# reLoaD_Base.net
KiCad netlist of a schematic drawn in EAGLE
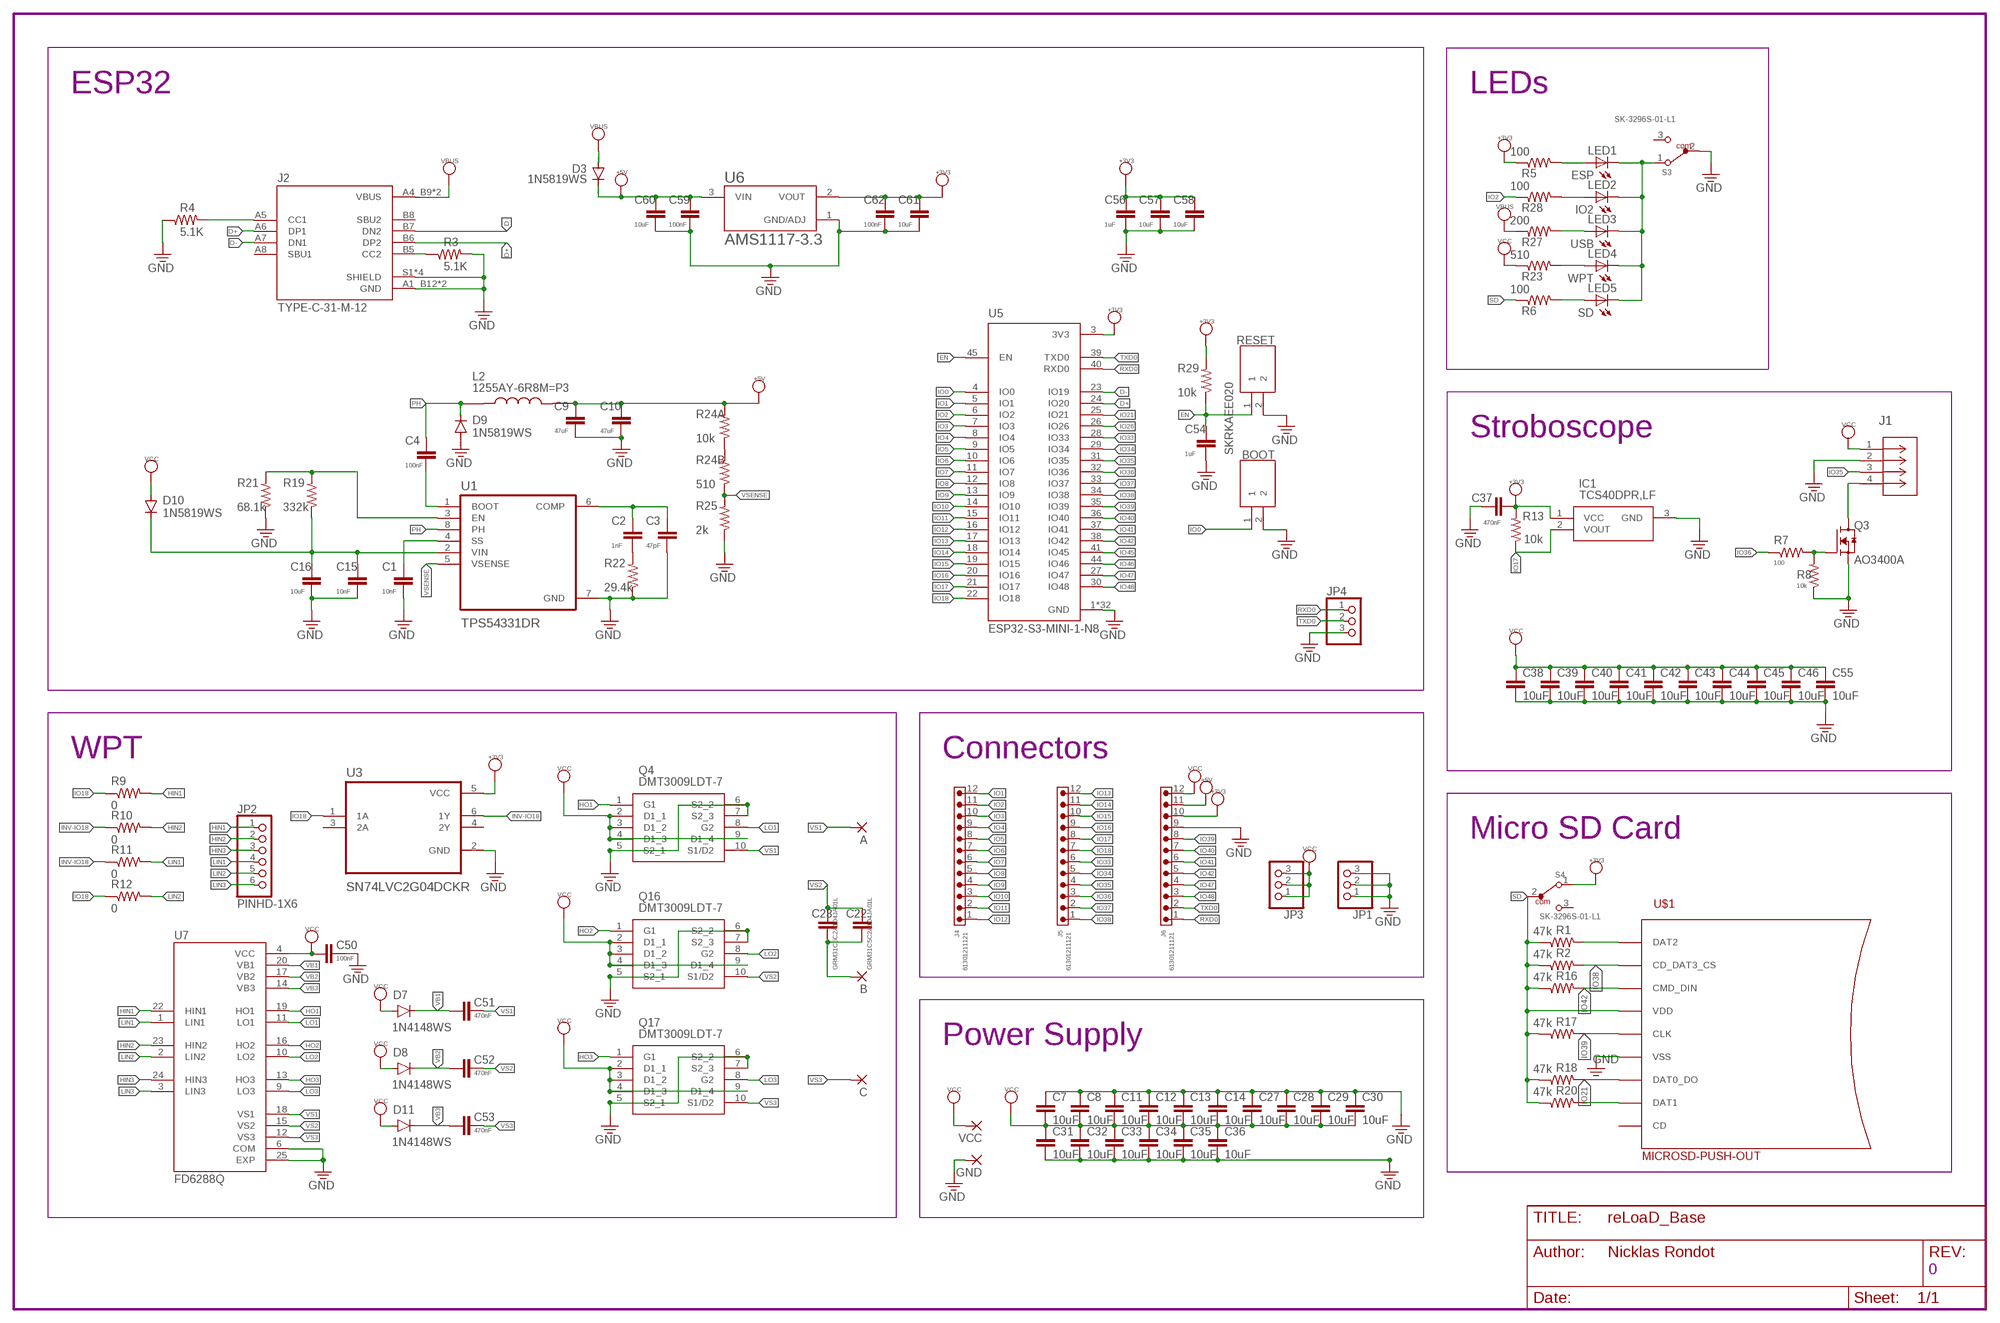
[diagram p0: schematic, sheet 1]

(export (version "E")
  (design (tool "Eeschema 10.0.6"))
  (components
    (comp (ref "A")
      (value "3,81/1,4")
      (footprint "eagle-import:3,81_1,4")
      (libsource (lib "eagle-import") (part "3,81/1,4"))
    )
    (comp (ref "B")
      (value "3,81/1,4")
      (footprint "eagle-import:3,81_1,4")
      (libsource (lib "eagle-import") (part "3,81/1,4"))
    )
    (comp (ref "BOOT")
      (value "SKRKAEE020")
      (footprint "eagle-import:SKRKAEE020")
      (fields (field (name "MOUSER_PART_NUMBER") "688-SKRKAEE020"))
      (libsource (lib "eagle-import") (part "SKRKAEE020"))
    )
    (comp (ref "C")
      (value "3,81/1,4")
      (footprint "eagle-import:3,81_1,4")
      (libsource (lib "eagle-import") (part "3,81/1,4"))
    )
    (comp (ref "C1")
      (value "10nF")
      (footprint "eagle-import:C0603K")
      (libsource (lib "eagle-import") (part "resistor_348_C-EUC0603K"))
    )
    (comp (ref "C2")
      (value "1nF")
      (footprint "eagle-import:C0603K")
      (libsource (lib "eagle-import") (part "resistor_348_C-EUC0603K"))
    )
    (comp (ref "C3")
      (value "47pF")
      (footprint "eagle-import:C0603K")
      (libsource (lib "eagle-import") (part "resistor_348_C-EUC0603K"))
    )
    (comp (ref "C4")
      (value "100nF")
      (footprint "eagle-import:C0603K")
      (libsource (lib "eagle-import") (part "resistor_348_C-EUC0603K"))
    )
    (comp (ref "C7")
      (value "10uF")
      (footprint "eagle-import:C0805K")
      (libsource (lib "eagle-import") (part "C-EUC0805K"))
    )
    (comp (ref "C8")
      (value "10uF")
      (footprint "eagle-import:C0805K")
      (libsource (lib "eagle-import") (part "C-EUC0805K"))
    )
    (comp (ref "C9")
      (value "47uF")
      (footprint "eagle-import:C0603K")
      (libsource (lib "eagle-import") (part "resistor_348_C-EUC0603K"))
    )
    (comp (ref "C10")
      (value "47uF")
      (footprint "eagle-import:C0603K")
      (libsource (lib "eagle-import") (part "resistor_348_C-EUC0603K"))
    )
    (comp (ref "C11")
      (value "10uF")
      (footprint "eagle-import:C0805K")
      (libsource (lib "eagle-import") (part "C-EUC0805K"))
    )
    (comp (ref "C12")
      (value "10uF")
      (footprint "eagle-import:C0805K")
      (libsource (lib "eagle-import") (part "C-EUC0805K"))
    )
    (comp (ref "C13")
      (value "10uF")
      (footprint "eagle-import:C0805K")
      (libsource (lib "eagle-import") (part "C-EUC0805K"))
    )
    (comp (ref "C14")
      (value "10uF")
      (footprint "eagle-import:C0805K")
      (libsource (lib "eagle-import") (part "C-EUC0805K"))
    )
    (comp (ref "C15")
      (value "10nF")
      (footprint "eagle-import:C0603K")
      (libsource (lib "eagle-import") (part "resistor_348_C-EUC0603K"))
    )
    (comp (ref "C16")
      (value "10uF")
      (footprint "eagle-import:C0603K")
      (libsource (lib "eagle-import") (part "resistor_348_C-EUC0603K"))
    )
    (comp (ref "C22")
      (value "GRM31C5C2A104JA01L")
      (footprint "eagle-import:C1206K")
      (libsource (lib "eagle-import") (part "C-EUC1206K"))
    )
    (comp (ref "C23")
      (value "GRM31C5C2A104JA01L")
      (footprint "eagle-import:C1206K")
      (libsource (lib "eagle-import") (part "C-EUC1206K"))
    )
    (comp (ref "C27")
      (value "10uF")
      (footprint "eagle-import:C0805K")
      (libsource (lib "eagle-import") (part "C-EUC0805K"))
    )
    (comp (ref "C28")
      (value "10uF")
      (footprint "eagle-import:C0805K")
      (libsource (lib "eagle-import") (part "C-EUC0805K"))
    )
    (comp (ref "C29")
      (value "10uF")
      (footprint "eagle-import:C0805K")
      (libsource (lib "eagle-import") (part "C-EUC0805K"))
    )
    (comp (ref "C30")
      (value "10uF")
      (footprint "eagle-import:C0805K")
      (libsource (lib "eagle-import") (part "C-EUC0805K"))
    )
    (comp (ref "C31")
      (value "10uF")
      (footprint "eagle-import:C0805K")
      (libsource (lib "eagle-import") (part "C-EUC0805K"))
    )
    (comp (ref "C32")
      (value "10uF")
      (footprint "eagle-import:C0805K")
      (libsource (lib "eagle-import") (part "C-EUC0805K"))
    )
    (comp (ref "C33")
      (value "10uF")
      (footprint "eagle-import:C0805K")
      (libsource (lib "eagle-import") (part "C-EUC0805K"))
    )
    (comp (ref "C34")
      (value "10uF")
      (footprint "eagle-import:C0805K")
      (libsource (lib "eagle-import") (part "C-EUC0805K"))
    )
    (comp (ref "C35")
      (value "10uF")
      (footprint "eagle-import:C0805K")
      (libsource (lib "eagle-import") (part "C-EUC0805K"))
    )
    (comp (ref "C36")
      (value "10uF")
      (footprint "eagle-import:C0805K")
      (libsource (lib "eagle-import") (part "C-EUC0805K"))
    )
    (comp (ref "C37")
      (value "470nF")
      (footprint "eagle-import:C0603K")
      (libsource (lib "eagle-import") (part "resistor_348_C-EUC0603K"))
    )
    (comp (ref "C38")
      (value "10uF")
      (footprint "eagle-import:C0805K")
      (libsource (lib "eagle-import") (part "C-EUC0805K"))
    )
    (comp (ref "C39")
      (value "10uF")
      (footprint "eagle-import:C0805K")
      (libsource (lib "eagle-import") (part "C-EUC0805K"))
    )
    (comp (ref "C40")
      (value "10uF")
      (footprint "eagle-import:C0805K")
      (libsource (lib "eagle-import") (part "C-EUC0805K"))
    )
    (comp (ref "C41")
      (value "10uF")
      (footprint "eagle-import:C0805K")
      (libsource (lib "eagle-import") (part "C-EUC0805K"))
    )
    (comp (ref "C42")
      (value "10uF")
      (footprint "eagle-import:C0805K")
      (libsource (lib "eagle-import") (part "C-EUC0805K"))
    )
    (comp (ref "C43")
      (value "10uF")
      (footprint "eagle-import:C0805K")
      (libsource (lib "eagle-import") (part "C-EUC0805K"))
    )
    (comp (ref "C44")
      (value "10uF")
      (footprint "eagle-import:C0805K")
      (libsource (lib "eagle-import") (part "C-EUC0805K"))
    )
    (comp (ref "C45")
      (value "10uF")
      (footprint "eagle-import:C0805K")
      (libsource (lib "eagle-import") (part "C-EUC0805K"))
    )
    (comp (ref "C46")
      (value "10uF")
      (footprint "eagle-import:C0805K")
      (libsource (lib "eagle-import") (part "C-EUC0805K"))
    )
    (comp (ref "C50")
      (value "100nF")
      (footprint "eagle-import:C0603K")
      (libsource (lib "eagle-import") (part "resistor_348_C-EUC0603K"))
    )
    (comp (ref "C51")
      (value "470nF")
      (footprint "eagle-import:C0603K")
      (libsource (lib "eagle-import") (part "resistor_348_C-EUC0603K"))
    )
    (comp (ref "C52")
      (value "470nF")
      (footprint "eagle-import:C0603K")
      (libsource (lib "eagle-import") (part "resistor_348_C-EUC0603K"))
    )
    (comp (ref "C53")
      (value "470nF")
      (footprint "eagle-import:C0603K")
      (libsource (lib "eagle-import") (part "resistor_348_C-EUC0603K"))
    )
    (comp (ref "C54")
      (value "1uF")
      (footprint "eagle-import:C0603K")
      (libsource (lib "eagle-import") (part "resistor_348_C-EUC0603K"))
    )
    (comp (ref "C55")
      (value "10uF")
      (footprint "eagle-import:C0805K")
      (libsource (lib "eagle-import") (part "C-EUC0805K"))
    )
    (comp (ref "C56")
      (value "1uF")
      (footprint "eagle-import:C0603K")
      (libsource (lib "eagle-import") (part "resistor_348_C-EUC0603K"))
    )
    (comp (ref "C57")
      (value "10uF")
      (footprint "eagle-import:C0603K")
      (libsource (lib "eagle-import") (part "resistor_348_C-EUC0603K"))
    )
    (comp (ref "C58")
      (value "10uF")
      (footprint "eagle-import:C0603K")
      (libsource (lib "eagle-import") (part "resistor_348_C-EUC0603K"))
    )
    (comp (ref "C59")
      (value "100nF")
      (footprint "eagle-import:C0603K")
      (libsource (lib "eagle-import") (part "resistor_348_C-EUC0603K"))
    )
    (comp (ref "C60")
      (value "10uF")
      (footprint "eagle-import:C0603K")
      (libsource (lib "eagle-import") (part "resistor_348_C-EUC0603K"))
    )
    (comp (ref "C61")
      (value "10uF")
      (footprint "eagle-import:C0603K")
      (libsource (lib "eagle-import") (part "resistor_348_C-EUC0603K"))
    )
    (comp (ref "C62")
      (value "100nF")
      (footprint "eagle-import:C0603K")
      (libsource (lib "eagle-import") (part "resistor_348_C-EUC0603K"))
    )
    (comp (ref "D3")
      (value "1N5819WS")
      (footprint "eagle-import:SOD323-W")
      (libsource (lib "eagle-import") (part "DIODE-SOD323-W"))
    )
    (comp (ref "D7")
      (value "1N4148WS")
      (footprint "eagle-import:SOD-323")
      (fields
        (field (name "DIGIKEY_PART_NUMBER") "1N4148WSFSTR-ND")
        (field (name "MANUFACTURER") "Diodes Incorporated")
        (field (name "CREATED_BY") "PCBLayout.com")
      )
      (libsource (lib "eagle-import") (part "1N4148WS"))
    )
    (comp (ref "D8")
      (value "1N4148WS")
      (footprint "eagle-import:SOD-323")
      (fields
        (field (name "DIGIKEY_PART_NUMBER") "1N4148WSFSTR-ND")
        (field (name "MANUFACTURER") "Diodes Incorporated")
        (field (name "CREATED_BY") "PCBLayout.com")
      )
      (libsource (lib "eagle-import") (part "1N4148WS"))
    )
    (comp (ref "D9")
      (value "1N5819WS")
      (footprint "eagle-import:SOD323-W")
      (libsource (lib "eagle-import") (part "DIODE-SOD323-W"))
    )
    (comp (ref "D10")
      (value "1N5819WS")
      (footprint "eagle-import:SOD323-W")
      (libsource (lib "eagle-import") (part "DIODE-SOD323-W"))
    )
    (comp (ref "D11")
      (value "1N4148WS")
      (footprint "eagle-import:SOD-323")
      (fields
        (field (name "DIGIKEY_PART_NUMBER") "1N4148WSFSTR-ND")
        (field (name "MANUFACTURER") "Diodes Incorporated")
        (field (name "CREATED_BY") "PCBLayout.com")
      )
      (libsource (lib "eagle-import") (part "1N4148WS"))
    )
    (comp (ref "GND")
      (value "3,81/1,4")
      (footprint "eagle-import:3,81_1,4")
      (libsource (lib "eagle-import") (part "3,81/1,4"))
    )
    (comp (ref "IC1")
      (value "TCS40DPR,LF")
      (footprint "eagle-import:SOTFL95P240X88-3N")
      (fields (field (name "MOUSER_PART_NUMBER") "757-TCS40DPRLF"))
      (libsource (lib "eagle-import") (part "TCS40DPR,LF"))
    )
    (comp (ref "J1")
      (value "S4B-XH-SM4-TBCONN4_S4B-XH_JST")
      (footprint "eagle-import:CONN4_S4B-XH_JST")
      (fields
        (field (name "MANUFACTURER_PART_NUMBER") "S4B-XH-SM4-TB")
        (field (name "COPYRIGHT") "Copyright (C) 2024 Ultra Librarian. All rights reserved.")
      )
      (libsource (lib "eagle-import") (part "S4B-XH-SM4-TBCONN4_S4B-XH_JST"))
    )
    (comp (ref "J2")
      (value "TYPE-C-31-M-12")
      (footprint "eagle-import:HRO_TYPE-C-31-M-12")
      (fields (field (name "MF") "HRO Electronics Co., Ltd."))
      (libsource (lib "eagle-import") (part "TYPE-C-31-M-12"))
    )
    (comp (ref "J4")
      (value "61301211121")
      (footprint "eagle-import:61301211121")
      (libsource (lib "eagle-import") (part "6130XX11121_61301211121"))
    )
    (comp (ref "J5")
      (value "61301211121")
      (footprint "eagle-import:61301211121")
      (libsource (lib "eagle-import") (part "6130XX11121_61301211121"))
    )
    (comp (ref "J6")
      (value "61301211121")
      (footprint "eagle-import:61301211121")
      (libsource (lib "eagle-import") (part "6130XX11121_61301211121"))
    )
    (comp (ref "JP1")
      (value "PINHD-1X3")
      (footprint "eagle-import:1X03")
      (libsource (lib "eagle-import") (part "PINHD-1X3"))
    )
    (comp (ref "JP2")
      (value "PINHD-1X6")
      (footprint "eagle-import:1X06")
      (libsource (lib "eagle-import") (part "PINHD-1X6"))
    )
    (comp (ref "JP3")
      (value "PINHD-1X3")
      (footprint "eagle-import:1X03")
      (libsource (lib "eagle-import") (part "PINHD-1X3"))
    )
    (comp (ref "JP4")
      (value "PINHD-1X3")
      (footprint "eagle-import:1X03")
      (libsource (lib "eagle-import") (part "PINHD-1X3"))
    )
    (comp (ref "L2")
      (value "1255AY-6R8M=P3")
      (footprint "eagle-import:IND_1255AY-6R8M=P3")
      (fields (field (name "MF") "Murata Electronics"))
      (libsource (lib "eagle-import") (part "1255AY-6R8M=P3"))
    )
    (comp (ref "LED1")
      (value "ESP")
      (footprint "eagle-import:CHIPLED_0805")
      (libsource (lib "eagle-import") (part "LEDCHIPLED_0805"))
    )
    (comp (ref "LED2")
      (value "IO2")
      (footprint "eagle-import:CHIPLED_0805")
      (libsource (lib "eagle-import") (part "LEDCHIPLED_0805"))
    )
    (comp (ref "LED3")
      (value "USB")
      (footprint "eagle-import:CHIPLED_0805")
      (libsource (lib "eagle-import") (part "LEDCHIPLED_0805"))
    )
    (comp (ref "LED4")
      (value "WPT")
      (footprint "eagle-import:CHIPLED_0805")
      (libsource (lib "eagle-import") (part "LEDCHIPLED_0805"))
    )
    (comp (ref "LED5")
      (value "SD")
      (footprint "eagle-import:CHIPLED_0805")
      (libsource (lib "eagle-import") (part "LEDCHIPLED_0805"))
    )
    (comp (ref "Q3")
      (value "AO3400A")
      (footprint "eagle-import:SOT95P280X125-3N")
      (fields (field (name "DIGIKEY_PART_NUMBER") "785-1000-2-ND") (field (name "MF") "Alpha &"))
      (libsource (lib "eagle-import") (part "AO3400A"))
    )
    (comp (ref "Q4")
      (value "DMT3009LDT-7")
      (footprint "eagle-import:DMT3009LDT7")
      (fields (field (name "MOUSER_PART_NUMBER") "621-DMT3009LDT-7"))
      (libsource (lib "eagle-import") (part "DMT3009LDT-7"))
    )
    (comp (ref "Q16")
      (value "DMT3009LDT-7")
      (footprint "eagle-import:DMT3009LDT7")
      (fields (field (name "MOUSER_PART_NUMBER") "621-DMT3009LDT-7"))
      (libsource (lib "eagle-import") (part "DMT3009LDT-7"))
    )
    (comp (ref "Q17")
      (value "DMT3009LDT-7")
      (footprint "eagle-import:DMT3009LDT7")
      (fields (field (name "MOUSER_PART_NUMBER") "621-DMT3009LDT-7"))
      (libsource (lib "eagle-import") (part "DMT3009LDT-7"))
    )
    (comp (ref "R1")
      (value "47k")
      (footprint "eagle-import:R0603")
      (libsource (lib "eagle-import") (part "R-US_R0603"))
    )
    (comp (ref "R2")
      (value "47k")
      (footprint "eagle-import:R0603")
      (libsource (lib "eagle-import") (part "R-US_R0603"))
    )
    (comp (ref "R3")
      (value "5.1K")
      (footprint "eagle-import:R0603")
      (libsource (lib "eagle-import") (part "R-US_R0603"))
    )
    (comp (ref "R4")
      (value "5.1K")
      (footprint "eagle-import:R0603")
      (libsource (lib "eagle-import") (part "R-US_R0603"))
    )
    (comp (ref "R5")
      (value "100")
      (footprint "eagle-import:R0603")
      (libsource (lib "eagle-import") (part "R-US_R0603"))
    )
    (comp (ref "R6")
      (value "100")
      (footprint "eagle-import:R0603")
      (libsource (lib "eagle-import") (part "R-US_R0603"))
    )
    (comp (ref "R7")
      (value "100")
      (footprint "eagle-import:R0603")
      (libsource (lib "eagle-import") (part "R-US_R0603"))
    )
    (comp (ref "R8")
      (value "10k")
      (footprint "eagle-import:R0603")
      (libsource (lib "eagle-import") (part "R-US_R0603"))
    )
    (comp (ref "R9")
      (value "0")
      (footprint "eagle-import:R0603")
      (libsource (lib "eagle-import") (part "R-US_R0603"))
    )
    (comp (ref "R10")
      (value "0")
      (footprint "eagle-import:R0603")
      (libsource (lib "eagle-import") (part "R-US_R0603"))
    )
    (comp (ref "R11")
      (value "0")
      (footprint "eagle-import:R0603")
      (libsource (lib "eagle-import") (part "R-US_R0603"))
    )
    (comp (ref "R12")
      (value "0")
      (footprint "eagle-import:R0603")
      (libsource (lib "eagle-import") (part "R-US_R0603"))
    )
    (comp (ref "R13")
      (value "10k")
      (footprint "eagle-import:R0603")
      (libsource (lib "eagle-import") (part "R-US_R0603"))
    )
    (comp (ref "R16")
      (value "47k")
      (footprint "eagle-import:R0603")
      (libsource (lib "eagle-import") (part "R-US_R0603"))
    )
    (comp (ref "R17")
      (value "47k")
      (footprint "eagle-import:R0603")
      (libsource (lib "eagle-import") (part "R-US_R0603"))
    )
    (comp (ref "R18")
      (value "47k")
      (footprint "eagle-import:R0603")
      (libsource (lib "eagle-import") (part "R-US_R0603"))
    )
    (comp (ref "R19")
      (value "332k")
      (footprint "eagle-import:R0603")
      (libsource (lib "eagle-import") (part "R-US_R0603"))
    )
    (comp (ref "R20")
      (value "47k")
      (footprint "eagle-import:R0603")
      (libsource (lib "eagle-import") (part "R-US_R0603"))
    )
    (comp (ref "R21")
      (value "68.1k")
      (footprint "eagle-import:R0603")
      (libsource (lib "eagle-import") (part "R-US_R0603"))
    )
    (comp (ref "R22")
      (value "29.4k")
      (footprint "eagle-import:R0603")
      (libsource (lib "eagle-import") (part "R-US_R0603"))
    )
    (comp (ref "R23")
      (value "510")
      (footprint "eagle-import:R0603")
      (libsource (lib "eagle-import") (part "R-US_R0603"))
    )
    (comp (ref "R24A")
      (value "10k")
      (footprint "eagle-import:R0603")
      (libsource (lib "eagle-import") (part "R-US_R0603"))
    )
    (comp (ref "R24B")
      (value "510")
      (footprint "eagle-import:R0603")
      (libsource (lib "eagle-import") (part "R-US_R0603"))
    )
    (comp (ref "R25")
      (value "2k")
      (footprint "eagle-import:R0603")
      (libsource (lib "eagle-import") (part "R-US_R0603"))
    )
    (comp (ref "R27")
      (value "200")
      (footprint "eagle-import:R0603")
      (libsource (lib "eagle-import") (part "R-US_R0603"))
    )
    (comp (ref "R28")
      (value "100")
      (footprint "eagle-import:R0603")
      (libsource (lib "eagle-import") (part "R-US_R0603"))
    )
    (comp (ref "R29")
      (value "10k")
      (footprint "eagle-import:R0603")
      (libsource (lib "eagle-import") (part "R-US_R0603"))
    )
    (comp (ref "RESET")
      (value "SKRKAEE020")
      (footprint "eagle-import:SKRKAEE020")
      (fields (field (name "MOUSER_PART_NUMBER") "688-SKRKAEE020"))
      (libsource (lib "eagle-import") (part "SKRKAEE020"))
    )
    (comp (ref "S3")
      (value "SK-3296S-01-L1")
      (footprint "eagle-import:450404015514")
      (libsource (lib "eagle-import") (part "450404015514"))
    )
    (comp (ref "S4")
      (value "SK-3296S-01-L1")
      (footprint "eagle-import:450404015514")
      (libsource (lib "eagle-import") (part "450404015514"))
    )
    (comp (ref "U$1")
      (value "MICROSD-PUSH-OUT")
      (footprint "eagle-import:MICROSD-PUSH-OUT")
      (libsource (lib "eagle-import") (part "MICROSD-PUSH-OUT"))
    )
    (comp (ref "U1")
      (value "TPS54331DR")
      (footprint "eagle-import:SOIC127P599X175-8N")
      (fields (field (name "MF") "Texas Instruments"))
      (libsource (lib "eagle-import") (part "TPS54331DR"))
    )
    (comp (ref "U3")
      (value "SN74LVC2G04DCKR")
      (footprint "eagle-import:SOT65P210X110-6N")
      (fields (field (name "MF") "Texas Instruments"))
      (libsource (lib "eagle-import") (part "SN74LVC2G04DCKR"))
    )
    (comp (ref "U5")
      (value "ESP32-S3-MINI-1-N8")
      (footprint "eagle-import:XCVR_ESP32-S3-MINI-1-N8")
      (fields (field (name "MF") "Espressif Systems"))
      (libsource (lib "eagle-import") (part "ESP32-S3-MINI-1-N8"))
    )
    (comp (ref "U6")
      (value "AMS1117-3.3")
      (footprint "eagle-import:SOT229P700X180-4N")
      (fields (field (name "MF") "Advanced Monolithic Systems"))
      (libsource (lib "eagle-import") (part "AMS1117-3.3"))
    )
    (comp (ref "U7")
      (value "FD6288Q")
      (footprint "eagle-import:QFN50P400X400X90-25N")
      (fields (field (name "MF") "Fortior Tech"))
      (libsource (lib "eagle-import") (part "FD6288Q"))
    )
    (comp (ref "VCC")
      (value "3,81/1,4")
      (footprint "eagle-import:3,81_1,4")
      (libsource (lib "eagle-import") (part "3,81/1,4"))
    )
  )
  (nets
    (net (code "1") (name "+3V3") (class "Default")
      (node (ref "C37") (pin "2") (pinfunction "2_2") (pintype "passive"))
      (node (ref "C56") (pin "1") (pinfunction "1_1") (pintype "passive"))
      (node (ref "C57") (pin "1") (pinfunction "1_1") (pintype "passive"))
      (node (ref "C58") (pin "1") (pinfunction "1_1") (pintype "passive"))
      (node (ref "C61") (pin "1") (pinfunction "1_1") (pintype "passive"))
      (node (ref "C62") (pin "1") (pinfunction "1_1") (pintype "passive"))
      (node (ref "IC1") (pin "1") (pinfunction "VCC_1") (pintype "bidirectional"))
      (node (ref "J6") (pin "10") (pinfunction "10_10") (pintype "passive"))
      (node (ref "R13") (pin "2") (pinfunction "2_2") (pintype "passive"))
      (node (ref "R29") (pin "2") (pinfunction "2_2") (pintype "passive"))
      (node (ref "R5") (pin "1") (pinfunction "1_1") (pintype "passive"))
      (node (ref "S4") (pin "1") (pinfunction "1_1") (pintype "passive"))
      (node (ref "U3") (pin "5") (pinfunction "VCC_5") (pintype "power_in"))
      (node (ref "U5") (pin "3") (pinfunction "3V3_3") (pintype "power_in"))
      (node (ref "U6") (pin "2") (pinfunction "VOUT_2") (pintype "output"))
    )
    (net (code "2") (name "+5V") (class "Default")
      (node (ref "C10") (pin "1") (pinfunction "1_1") (pintype "passive"))
      (node (ref "C59") (pin "1") (pinfunction "1_1") (pintype "passive"))
      (node (ref "C60") (pin "1") (pinfunction "1_1") (pintype "passive"))
      (node (ref "C9") (pin "1") (pinfunction "1_1") (pintype "passive"))
      (node (ref "D3") (pin "C") (pinfunction "C_C") (pintype "passive"))
      (node (ref "J6") (pin "11") (pinfunction "11_11") (pintype "passive"))
      (node (ref "L2") (pin "2") (pinfunction "2_2") (pintype "passive"))
      (node (ref "R24A") (pin "2") (pinfunction "2_2") (pintype "passive"))
      (node (ref "U6") (pin "3") (pinfunction "VIN_3") (pintype "input"))
    )
    (net (code "3") (name "D+") (class "Default")
      (node (ref "J2") (pin "A6") (pinfunction "DP1_A6") (pintype "bidirectional"))
      (node (ref "J2") (pin "B6") (pinfunction "DP2_B6") (pintype "bidirectional"))
      (node (ref "U5") (pin "24") (pinfunction "IO20_24") (pintype "bidirectional"))
    )
    (net (code "4") (name "D-") (class "Default")
      (node (ref "J2") (pin "A7") (pinfunction "DN1_A7") (pintype "bidirectional"))
      (node (ref "J2") (pin "B7") (pinfunction "DN2_B7") (pintype "bidirectional"))
      (node (ref "U5") (pin "23") (pinfunction "IO19_23") (pintype "bidirectional"))
    )
    (net (code "5") (name "EN") (class "Default")
      (node (ref "C54") (pin "1") (pinfunction "1_1") (pintype "passive"))
      (node (ref "R29") (pin "1") (pinfunction "1_1") (pintype "passive"))
      (node (ref "RESET") (pin "1") (pinfunction "1_1") (pintype "bidirectional"))
      (node (ref "U5") (pin "45") (pinfunction "EN_45") (pintype "input"))
    )
    (net (code "6") (name "GND") (class "Default")
      (node (ref "BOOT") (pin "2") (pinfunction "2_2") (pintype "bidirectional"))
      (node (ref "C1") (pin "2") (pinfunction "2_2") (pintype "passive"))
      (node (ref "C10") (pin "2") (pinfunction "2_2") (pintype "passive"))
      (node (ref "C11") (pin "1") (pinfunction "1_1") (pintype "passive"))
      (node (ref "C12") (pin "1") (pinfunction "1_1") (pintype "passive"))
      (node (ref "C13") (pin "1") (pinfunction "1_1") (pintype "passive"))
      (node (ref "C14") (pin "1") (pinfunction "1_1") (pintype "passive"))
      (node (ref "C15") (pin "2") (pinfunction "2_2") (pintype "passive"))
      (node (ref "C16") (pin "2") (pinfunction "2_2") (pintype "passive"))
      (node (ref "C27") (pin "1") (pinfunction "1_1") (pintype "passive"))
      (node (ref "C28") (pin "1") (pinfunction "1_1") (pintype "passive"))
      (node (ref "C29") (pin "1") (pinfunction "1_1") (pintype "passive"))
      (node (ref "C3") (pin "2") (pinfunction "2_2") (pintype "passive"))
      (node (ref "C30") (pin "1") (pinfunction "1_1") (pintype "passive"))
      (node (ref "C31") (pin "2") (pinfunction "2_2") (pintype "passive"))
      (node (ref "C32") (pin "2") (pinfunction "2_2") (pintype "passive"))
      (node (ref "C33") (pin "2") (pinfunction "2_2") (pintype "passive"))
      (node (ref "C34") (pin "2") (pinfunction "2_2") (pintype "passive"))
      (node (ref "C35") (pin "2") (pinfunction "2_2") (pintype "passive"))
      (node (ref "C36") (pin "2") (pinfunction "2_2") (pintype "passive"))
      (node (ref "C37") (pin "1") (pinfunction "1_1") (pintype "passive"))
      (node (ref "C38") (pin "2") (pinfunction "2_2") (pintype "passive"))
      (node (ref "C39") (pin "2") (pinfunction "2_2") (pintype "passive"))
      (node (ref "C40") (pin "2") (pinfunction "2_2") (pintype "passive"))
      (node (ref "C41") (pin "2") (pinfunction "2_2") (pintype "passive"))
      (node (ref "C42") (pin "2") (pinfunction "2_2") (pintype "passive"))
      (node (ref "C43") (pin "2") (pinfunction "2_2") (pintype "passive"))
      (node (ref "C44") (pin "2") (pinfunction "2_2") (pintype "passive"))
      (node (ref "C45") (pin "2") (pinfunction "2_2") (pintype "passive"))
      (node (ref "C46") (pin "2") (pinfunction "2_2") (pintype "passive"))
      (node (ref "C50") (pin "1") (pinfunction "1_1") (pintype "passive"))
      (node (ref "C54") (pin "2") (pinfunction "2_2") (pintype "passive"))
      (node (ref "C55") (pin "2") (pinfunction "2_2") (pintype "passive"))
      (node (ref "C56") (pin "2") (pinfunction "2_2") (pintype "passive"))
      (node (ref "C57") (pin "2") (pinfunction "2_2") (pintype "passive"))
      (node (ref "C58") (pin "2") (pinfunction "2_2") (pintype "passive"))
      (node (ref "C59") (pin "2") (pinfunction "2_2") (pintype "passive"))
      (node (ref "C60") (pin "2") (pinfunction "2_2") (pintype "passive"))
      (node (ref "C61") (pin "2") (pinfunction "2_2") (pintype "passive"))
      (node (ref "C62") (pin "2") (pinfunction "2_2") (pintype "passive"))
      (node (ref "C7") (pin "1") (pinfunction "1_1") (pintype "passive"))
      (node (ref "C8") (pin "1") (pinfunction "1_1") (pintype "passive"))
      (node (ref "C9") (pin "2") (pinfunction "2_2") (pintype "passive"))
      (node (ref "D9") (pin "A") (pinfunction "A_A") (pintype "passive"))
      (node (ref "GND") (pin "1") (pinfunction "P_1") (pintype "passive"))
      (node (ref "IC1") (pin "3") (pinfunction "GND_3") (pintype "bidirectional"))
      (node (ref "J1") (pin "2") (pinfunction "2_2") (pintype "passive"))
      (node (ref "J2") (pin "A1_B12") (pinfunction "GND_A1_B12") (pintype "power_in"))
      (node (ref "J2") (pin "B1_A12") (pinfunction "GND_B1_A12") (pintype "power_in"))
      (node (ref "J2") (pin "S1") (pinfunction "SHIELD_S1") (pintype "passive"))
      (node (ref "J2") (pin "S2") (pinfunction "SHIELD_S2") (pintype "passive"))
      (node (ref "J2") (pin "S3") (pinfunction "SHIELD_S3") (pintype "passive"))
      (node (ref "J2") (pin "S4") (pinfunction "SHIELD_S4") (pintype "passive"))
      (node (ref "J6") (pin "9") (pinfunction "9_9") (pintype "passive"))
      (node (ref "JP1") (pin "1") (pinfunction "1_1") (pintype "passive"))
      (node (ref "JP1") (pin "2") (pinfunction "2_2") (pintype "passive"))
      (node (ref "JP1") (pin "3") (pinfunction "3_3") (pintype "passive"))
      (node (ref "JP4") (pin "3") (pinfunction "3_3") (pintype "passive"))
      (node (ref "Q16") (pin "5") (pinfunction "S2_1_5") (pintype "bidirectional"))
      (node (ref "Q16") (pin "6") (pinfunction "S2_2_6") (pintype "bidirectional"))
      (node (ref "Q16") (pin "7") (pinfunction "S2_3_7") (pintype "bidirectional"))
      (node (ref "Q17") (pin "5") (pinfunction "S2_1_5") (pintype "bidirectional"))
      (node (ref "Q17") (pin "6") (pinfunction "S2_2_6") (pintype "bidirectional"))
      (node (ref "Q17") (pin "7") (pinfunction "S2_3_7") (pintype "bidirectional"))
      (node (ref "Q3") (pin "2") (pinfunction "S_2") (pintype "passive"))
      (node (ref "Q4") (pin "5") (pinfunction "S2_1_5") (pintype "bidirectional"))
      (node (ref "Q4") (pin "6") (pinfunction "S2_2_6") (pintype "bidirectional"))
      (node (ref "Q4") (pin "7") (pinfunction "S2_3_7") (pintype "bidirectional"))
      (node (ref "R21") (pin "1") (pinfunction "1_1") (pintype "passive"))
      (node (ref "R22") (pin "1") (pinfunction "1_1") (pintype "passive"))
      (node (ref "R25") (pin "1") (pinfunction "1_1") (pintype "passive"))
      (node (ref "R3") (pin "2") (pinfunction "2_2") (pintype "passive"))
      (node (ref "R4") (pin "1") (pinfunction "1_1") (pintype "passive"))
      (node (ref "R8") (pin "1") (pinfunction "1_1") (pintype "passive"))
      (node (ref "RESET") (pin "2") (pinfunction "2_2") (pintype "bidirectional"))
      (node (ref "S3") (pin "2") (pinfunction "2_2") (pintype "passive"))
      (node (ref "U$1") (pin "6") (pinfunction "VSS_6") (pintype "bidirectional"))
      (node (ref "U$1") (pin "G1") (pinfunction "VSS_G1") (pintype "bidirectional"))
      (node (ref "U$1") (pin "G2") (pinfunction "VSS_G2") (pintype "bidirectional"))
      (node (ref "U$1") (pin "G3") (pinfunction "VSS_G3") (pintype "bidirectional"))
      (node (ref "U$1") (pin "G4") (pinfunction "VSS_G4") (pintype "bidirectional"))
      (node (ref "U1") (pin "7") (pinfunction "GND_7") (pintype "power_in"))
      (node (ref "U3") (pin "2") (pinfunction "GND_2") (pintype "power_in"))
      (node (ref "U5") (pin "1") (pinfunction "GND_1") (pintype "power_in"))
      (node (ref "U5") (pin "2") (pinfunction "GND_2") (pintype "power_in"))
      (node (ref "U5") (pin "42") (pinfunction "GND_42") (pintype "power_in"))
      (node (ref "U5") (pin "43") (pinfunction "GND_43") (pintype "power_in"))
      (node (ref "U5") (pin "46") (pinfunction "GND_46") (pintype "power_in"))
      (node (ref "U5") (pin "47") (pinfunction "GND_47") (pintype "power_in"))
      (node (ref "U5") (pin "48") (pinfunction "GND_48") (pintype "power_in"))
      (node (ref "U5") (pin "49") (pinfunction "GND_49") (pintype "power_in"))
      (node (ref "U5") (pin "50") (pinfunction "GND_50") (pintype "power_in"))
      (node (ref "U5") (pin "51") (pinfunction "GND_51") (pintype "power_in"))
      (node (ref "U5") (pin "52") (pinfunction "GND_52") (pintype "power_in"))
      (node (ref "U5") (pin "53") (pinfunction "GND_53") (pintype "power_in"))
      (node (ref "U5") (pin "54") (pinfunction "GND_54") (pintype "power_in"))
      (node (ref "U5") (pin "55") (pinfunction "GND_55") (pintype "power_in"))
      (node (ref "U5") (pin "56") (pinfunction "GND_56") (pintype "power_in"))
      (node (ref "U5") (pin "57") (pinfunction "GND_57") (pintype "power_in"))
      (node (ref "U5") (pin "58") (pinfunction "GND_58") (pintype "power_in"))
      (node (ref "U5") (pin "59") (pinfunction "GND_59") (pintype "power_in"))
      (node (ref "U5") (pin "60") (pinfunction "GND_60") (pintype "power_in"))
      (node (ref "U5") (pin "61") (pinfunction "GND_61") (pintype "power_in"))
      (node (ref "U5") (pin "61_1") (pinfunction "GND_61_1") (pintype "power_in"))
      (node (ref "U5") (pin "61_2") (pinfunction "GND_61_2") (pintype "power_in"))
      (node (ref "U5") (pin "61_3") (pinfunction "GND_61_3") (pintype "power_in"))
      (node (ref "U5") (pin "61_4") (pinfunction "GND_61_4") (pintype "power_in"))
      (node (ref "U5") (pin "61_5") (pinfunction "GND_61_5") (pintype "power_in"))
      (node (ref "U5") (pin "61_6") (pinfunction "GND_61_6") (pintype "power_in"))
      (node (ref "U5") (pin "61_7") (pinfunction "GND_61_7") (pintype "power_in"))
      (node (ref "U5") (pin "61_8") (pinfunction "GND_61_8") (pintype "power_in"))
      (node (ref "U5") (pin "62") (pinfunction "GND_62") (pintype "power_in"))
      (node (ref "U5") (pin "63") (pinfunction "GND_63") (pintype "power_in"))
      (node (ref "U5") (pin "64") (pinfunction "GND_64") (pintype "power_in"))
      (node (ref "U5") (pin "65") (pinfunction "GND_65") (pintype "power_in"))
      (node (ref "U6") (pin "1") (pinfunction "GND/ADJ_1") (pintype "power_in"))
      (node (ref "U7") (pin "25") (pinfunction "EXP_25") (pintype "power_in"))
      (node (ref "U7") (pin "6") (pinfunction "COM_6") (pintype "power_in"))
    )
    (net (code "7") (name "HIN1") (class "Default")
      (node (ref "JP2") (pin "1") (pinfunction "1_1") (pintype "passive"))
      (node (ref "R9") (pin "2") (pinfunction "2_2") (pintype "passive"))
      (node (ref "U7") (pin "22") (pinfunction "HIN1_22") (pintype "input"))
    )
    (net (code "8") (name "HIN2") (class "Default")
      (node (ref "JP2") (pin "2") (pinfunction "2_2") (pintype "passive"))
      (node (ref "R10") (pin "2") (pinfunction "2_2") (pintype "passive"))
      (node (ref "U7") (pin "23") (pinfunction "HIN2_23") (pintype "input"))
    )
    (net (code "9") (name "HIN3") (class "Default")
      (node (ref "JP2") (pin "3") (pinfunction "3_3") (pintype "passive"))
      (node (ref "U7") (pin "24") (pinfunction "HIN3_24") (pintype "input"))
    )
    (net (code "10") (name "HO1") (class "Default")
      (node (ref "Q4") (pin "1") (pinfunction "G1_1") (pintype "bidirectional"))
      (node (ref "U7") (pin "19") (pinfunction "HO1_19") (pintype "output"))
    )
    (net (code "11") (name "HO2") (class "Default")
      (node (ref "Q16") (pin "1") (pinfunction "G1_1") (pintype "bidirectional"))
      (node (ref "U7") (pin "16") (pinfunction "HO2_16") (pintype "output"))
    )
    (net (code "12") (name "HO3") (class "Default")
      (node (ref "Q17") (pin "1") (pinfunction "G1_1") (pintype "bidirectional"))
      (node (ref "U7") (pin "13") (pinfunction "HO3_13") (pintype "output"))
    )
    (net (code "13") (name "INV-IO18") (class "Default")
      (node (ref "R10") (pin "1") (pinfunction "1_1") (pintype "passive"))
      (node (ref "R11") (pin "1") (pinfunction "1_1") (pintype "passive"))
      (node (ref "U3") (pin "6") (pinfunction "1Y_6") (pintype "output"))
    )
    (net (code "14") (name "IO0") (class "Default")
      (node (ref "BOOT") (pin "1") (pinfunction "1_1") (pintype "bidirectional"))
      (node (ref "U5") (pin "4") (pinfunction "IO0_4") (pintype "bidirectional"))
    )
    (net (code "15") (name "IO1") (class "Default")
      (node (ref "J4") (pin "12") (pinfunction "12_12") (pintype "passive"))
      (node (ref "U5") (pin "5") (pinfunction "IO1_5") (pintype "bidirectional"))
    )
    (net (code "16") (name "IO2") (class "Default")
      (node (ref "J4") (pin "11") (pinfunction "11_11") (pintype "passive"))
      (node (ref "R28") (pin "1") (pinfunction "1_1") (pintype "passive"))
      (node (ref "U5") (pin "6") (pinfunction "IO2_6") (pintype "bidirectional"))
    )
    (net (code "17") (name "IO3") (class "Default")
      (node (ref "J4") (pin "10") (pinfunction "10_10") (pintype "passive"))
      (node (ref "U5") (pin "7") (pinfunction "IO3_7") (pintype "bidirectional"))
    )
    (net (code "18") (name "IO4") (class "Default")
      (node (ref "J4") (pin "9") (pinfunction "9_9") (pintype "passive"))
      (node (ref "U5") (pin "8") (pinfunction "IO4_8") (pintype "bidirectional"))
    )
    (net (code "19") (name "IO5") (class "Default")
      (node (ref "J4") (pin "8") (pinfunction "8_8") (pintype "passive"))
      (node (ref "U5") (pin "9") (pinfunction "IO5_9") (pintype "bidirectional"))
    )
    (net (code "20") (name "IO6") (class "Default")
      (node (ref "J4") (pin "7") (pinfunction "7_7") (pintype "passive"))
      (node (ref "U5") (pin "10") (pinfunction "IO6_10") (pintype "bidirectional"))
    )
    (net (code "21") (name "IO7") (class "Default")
      (node (ref "J4") (pin "6") (pinfunction "6_6") (pintype "passive"))
      (node (ref "U5") (pin "11") (pinfunction "IO7_11") (pintype "bidirectional"))
    )
    (net (code "22") (name "IO8") (class "Default")
      (node (ref "J4") (pin "5") (pinfunction "5_5") (pintype "passive"))
      (node (ref "U5") (pin "12") (pinfunction "IO8_12") (pintype "bidirectional"))
    )
    (net (code "23") (name "IO9") (class "Default")
      (node (ref "J4") (pin "4") (pinfunction "4_4") (pintype "passive"))
      (node (ref "U5") (pin "13") (pinfunction "IO9_13") (pintype "bidirectional"))
    )
    (net (code "24") (name "IO10") (class "Default")
      (node (ref "J4") (pin "3") (pinfunction "3_3") (pintype "passive"))
      (node (ref "U5") (pin "14") (pinfunction "IO10_14") (pintype "bidirectional"))
    )
    (net (code "25") (name "IO11") (class "Default")
      (node (ref "J4") (pin "2") (pinfunction "2_2") (pintype "passive"))
      (node (ref "U5") (pin "15") (pinfunction "IO11_15") (pintype "bidirectional"))
    )
    (net (code "26") (name "IO12") (class "Default")
      (node (ref "J4") (pin "1") (pinfunction "1_1") (pintype "passive"))
      (node (ref "U5") (pin "16") (pinfunction "IO12_16") (pintype "bidirectional"))
    )
    (net (code "27") (name "IO13") (class "Default")
      (node (ref "J5") (pin "12") (pinfunction "12_12") (pintype "passive"))
      (node (ref "U5") (pin "17") (pinfunction "IO13_17") (pintype "bidirectional"))
    )
    (net (code "28") (name "IO14") (class "Default")
      (node (ref "J5") (pin "11") (pinfunction "11_11") (pintype "passive"))
      (node (ref "U5") (pin "18") (pinfunction "IO14_18") (pintype "bidirectional"))
    )
    (net (code "29") (name "IO15") (class "Default")
      (node (ref "J5") (pin "10") (pinfunction "10_10") (pintype "passive"))
      (node (ref "U5") (pin "19") (pinfunction "IO15_19") (pintype "bidirectional"))
    )
    (net (code "30") (name "IO16") (class "Default")
      (node (ref "J5") (pin "9") (pinfunction "9_9") (pintype "passive"))
      (node (ref "U5") (pin "20") (pinfunction "IO16_20") (pintype "bidirectional"))
    )
    (net (code "31") (name "IO17") (class "Default")
      (node (ref "IC1") (pin "2") (pinfunction "VOUT_2") (pintype "bidirectional"))
      (node (ref "J5") (pin "8") (pinfunction "8_8") (pintype "passive"))
      (node (ref "R13") (pin "1") (pinfunction "1_1") (pintype "passive"))
      (node (ref "U5") (pin "21") (pinfunction "IO17_21") (pintype "bidirectional"))
    )
    (net (code "32") (name "IO18") (class "Default")
      (node (ref "J5") (pin "7") (pinfunction "7_7") (pintype "passive"))
      (node (ref "R12") (pin "1") (pinfunction "1_1") (pintype "passive"))
      (node (ref "R9") (pin "1") (pinfunction "1_1") (pintype "passive"))
      (node (ref "U3") (pin "1") (pinfunction "1A_1") (pintype "input"))
      (node (ref "U5") (pin "22") (pinfunction "IO18_22") (pintype "bidirectional"))
    )
    (net (code "33") (name "IO21") (class "Default")
      (node (ref "R18") (pin "2") (pinfunction "2_2") (pintype "passive"))
      (node (ref "U$1") (pin "7") (pinfunction "DAT0_DO_7") (pintype "bidirectional"))
      (node (ref "U5") (pin "25") (pinfunction "IO21_25") (pintype "bidirectional"))
    )
    (net (code "34") (name "IO26") (class "Default")
      (node (ref "U5") (pin "26") (pinfunction "IO26_26") (pintype "bidirectional"))
    )
    (net (code "35") (name "IO33") (class "Default")
      (node (ref "J5") (pin "6") (pinfunction "6_6") (pintype "passive"))
      (node (ref "U5") (pin "28") (pinfunction "IO33_28") (pintype "bidirectional"))
    )
    (net (code "36") (name "IO34") (class "Default")
      (node (ref "J5") (pin "5") (pinfunction "5_5") (pintype "passive"))
      (node (ref "U5") (pin "29") (pinfunction "IO34_29") (pintype "bidirectional"))
    )
    (net (code "37") (name "IO35") (class "Default")
      (node (ref "J1") (pin "3") (pinfunction "3_3") (pintype "passive"))
      (node (ref "J5") (pin "4") (pinfunction "4_4") (pintype "passive"))
      (node (ref "U5") (pin "31") (pinfunction "IO35_31") (pintype "bidirectional"))
    )
    (net (code "38") (name "IO36") (class "Default")
      (node (ref "J5") (pin "3") (pinfunction "3_3") (pintype "passive"))
      (node (ref "R7") (pin "1") (pinfunction "1_1") (pintype "passive"))
      (node (ref "U5") (pin "32") (pinfunction "IO36_32") (pintype "bidirectional"))
    )
    (net (code "39") (name "IO37") (class "Default")
      (node (ref "J5") (pin "2") (pinfunction "2_2") (pintype "passive"))
      (node (ref "U5") (pin "33") (pinfunction "IO37_33") (pintype "bidirectional"))
    )
    (net (code "40") (name "IO38") (class "Default")
      (node (ref "J5") (pin "1") (pinfunction "1_1") (pintype "passive"))
      (node (ref "R2") (pin "2") (pinfunction "2_2") (pintype "passive"))
      (node (ref "U$1") (pin "2") (pinfunction "CD_DAT3_CS_2") (pintype "bidirectional"))
      (node (ref "U5") (pin "34") (pinfunction "IO38_34") (pintype "bidirectional"))
    )
    (net (code "41") (name "IO39") (class "Default")
      (node (ref "J6") (pin "8") (pinfunction "8_8") (pintype "passive"))
      (node (ref "R17") (pin "2") (pinfunction "2_2") (pintype "passive"))
      (node (ref "U$1") (pin "5") (pinfunction "CLK_5") (pintype "bidirectional"))
      (node (ref "U5") (pin "35") (pinfunction "IO39_35") (pintype "bidirectional"))
    )
    (net (code "42") (name "IO40") (class "Default")
      (node (ref "J6") (pin "7") (pinfunction "7_7") (pintype "passive"))
      (node (ref "U5") (pin "36") (pinfunction "IO40_36") (pintype "bidirectional"))
    )
    (net (code "43") (name "IO41") (class "Default")
      (node (ref "J6") (pin "6") (pinfunction "6_6") (pintype "passive"))
      (node (ref "U5") (pin "37") (pinfunction "IO41_37") (pintype "bidirectional"))
    )
    (net (code "44") (name "IO42") (class "Default")
      (node (ref "J6") (pin "5") (pinfunction "5_5") (pintype "passive"))
      (node (ref "R16") (pin "2") (pinfunction "2_2") (pintype "passive"))
      (node (ref "U$1") (pin "3") (pinfunction "CMD_DIN_3") (pintype "bidirectional"))
      (node (ref "U5") (pin "38") (pinfunction "IO42_38") (pintype "bidirectional"))
    )
    (net (code "45") (name "IO45") (class "Default")
      (node (ref "U5") (pin "41") (pinfunction "IO45_41") (pintype "bidirectional"))
    )
    (net (code "46") (name "IO46") (class "Default")
      (node (ref "U5") (pin "44") (pinfunction "IO46_44") (pintype "bidirectional"))
    )
    (net (code "47") (name "IO47") (class "Default")
      (node (ref "J6") (pin "4") (pinfunction "4_4") (pintype "passive"))
      (node (ref "U5") (pin "27") (pinfunction "IO47_27") (pintype "bidirectional"))
    )
    (net (code "48") (name "IO48") (class "Default")
      (node (ref "J6") (pin "3") (pinfunction "3_3") (pintype "passive"))
      (node (ref "U5") (pin "30") (pinfunction "IO48_30") (pintype "bidirectional"))
    )
    (net (code "49") (name "LIN1") (class "Default")
      (node (ref "JP2") (pin "4") (pinfunction "4_4") (pintype "passive"))
      (node (ref "R11") (pin "2") (pinfunction "2_2") (pintype "passive"))
      (node (ref "U7") (pin "1") (pinfunction "LIN1_1") (pintype "input"))
    )
    (net (code "50") (name "LIN2") (class "Default")
      (node (ref "JP2") (pin "5") (pinfunction "5_5") (pintype "passive"))
      (node (ref "R12") (pin "2") (pinfunction "2_2") (pintype "passive"))
      (node (ref "U7") (pin "2") (pinfunction "LIN2_2") (pintype "input"))
    )
    (net (code "51") (name "LIN3") (class "Default")
      (node (ref "JP2") (pin "6") (pinfunction "6_6") (pintype "passive"))
      (node (ref "U7") (pin "3") (pinfunction "LIN3_3") (pintype "input"))
    )
    (net (code "52") (name "LO1") (class "Default")
      (node (ref "Q4") (pin "8") (pinfunction "G2_8") (pintype "bidirectional"))
      (node (ref "U7") (pin "11") (pinfunction "LO1_11") (pintype "output"))
    )
    (net (code "53") (name "LO2") (class "Default")
      (node (ref "Q16") (pin "8") (pinfunction "G2_8") (pintype "bidirectional"))
      (node (ref "U7") (pin "10") (pinfunction "LO2_10") (pintype "output"))
    )
    (net (code "54") (name "LO3") (class "Default")
      (node (ref "Q17") (pin "8") (pinfunction "G2_8") (pintype "bidirectional"))
      (node (ref "U7") (pin "9") (pinfunction "LO3_9") (pintype "output"))
    )
    (net (code "55") (name "Net-(B-P)") (class "Default")
      (node (ref "B") (pin "1") (pinfunction "P_1") (pintype "passive"))
      (node (ref "C22") (pin "1") (pinfunction "1_1") (pintype "passive"))
      (node (ref "C23") (pin "1") (pinfunction "1_1") (pintype "passive"))
    )
    (net (code "56") (name "Net-(C2-Pad2)") (class "Default")
      (node (ref "C2") (pin "2") (pinfunction "2_2") (pintype "passive"))
      (node (ref "R22") (pin "2") (pinfunction "2_2") (pintype "passive"))
    )
    (net (code "57") (name "Net-(J2-CC1)") (class "Default")
      (node (ref "J2") (pin "A5") (pinfunction "CC1_A5") (pintype "bidirectional"))
      (node (ref "R4") (pin "2") (pinfunction "2_2") (pintype "passive"))
    )
    (net (code "58") (name "Net-(J2-CC2)") (class "Default")
      (node (ref "J2") (pin "B5") (pinfunction "CC2_B5") (pintype "bidirectional"))
      (node (ref "R3") (pin "1") (pinfunction "1_1") (pintype "passive"))
    )
    (net (code "59") (name "Net-(LED1-PadA)") (class "Default")
      (node (ref "LED1") (pin "A") (pinfunction "A_A") (pintype "passive"))
      (node (ref "R5") (pin "2") (pinfunction "2_2") (pintype "passive"))
    )
    (net (code "60") (name "Net-(LED1-PadC)") (class "Default")
      (node (ref "LED1") (pin "C") (pinfunction "C_C") (pintype "passive"))
      (node (ref "LED2") (pin "C") (pinfunction "C_C") (pintype "passive"))
      (node (ref "LED3") (pin "C") (pinfunction "C_C") (pintype "passive"))
      (node (ref "LED4") (pin "C") (pinfunction "C_C") (pintype "passive"))
      (node (ref "LED5") (pin "C") (pinfunction "C_C") (pintype "passive"))
      (node (ref "S3") (pin "1") (pinfunction "1_1") (pintype "passive"))
    )
    (net (code "61") (name "Net-(LED2-PadA)") (class "Default")
      (node (ref "LED2") (pin "A") (pinfunction "A_A") (pintype "passive"))
      (node (ref "R28") (pin "2") (pinfunction "2_2") (pintype "passive"))
    )
    (net (code "62") (name "Net-(LED3-PadA)") (class "Default")
      (node (ref "LED3") (pin "A") (pinfunction "A_A") (pintype "passive"))
      (node (ref "R27") (pin "2") (pinfunction "2_2") (pintype "passive"))
    )
    (net (code "63") (name "Net-(LED4-PadA)") (class "Default")
      (node (ref "LED4") (pin "A") (pinfunction "A_A") (pintype "passive"))
      (node (ref "R23") (pin "2") (pinfunction "2_2") (pintype "passive"))
    )
    (net (code "64") (name "Net-(LED5-PadA)") (class "Default")
      (node (ref "LED5") (pin "A") (pinfunction "A_A") (pintype "passive"))
      (node (ref "R6") (pin "2") (pinfunction "2_2") (pintype "passive"))
    )
    (net (code "65") (name "Net-(Q3-D)") (class "Default")
      (node (ref "J1") (pin "4") (pinfunction "4_4") (pintype "passive"))
      (node (ref "Q3") (pin "3") (pinfunction "D_3") (pintype "passive"))
    )
    (net (code "66") (name "Net-(Q3-G)") (class "Default")
      (node (ref "Q3") (pin "1") (pinfunction "G_1") (pintype "passive"))
      (node (ref "R7") (pin "2") (pinfunction "2_2") (pintype "passive"))
      (node (ref "R8") (pin "2") (pinfunction "2_2") (pintype "passive"))
    )
    (net (code "67") (name "Net-(R24A-Pad1)") (class "Default")
      (node (ref "R24A") (pin "1") (pinfunction "1_1") (pintype "passive"))
      (node (ref "R24B") (pin "2") (pinfunction "2_2") (pintype "passive"))
    )
    (net (code "68") (name "Net-(U$1-DAT1)") (class "Default")
      (node (ref "R20") (pin "2") (pinfunction "2_2") (pintype "passive"))
      (node (ref "U$1") (pin "8") (pinfunction "DAT1_8") (pintype "bidirectional"))
    )
    (net (code "69") (name "Net-(U$1-DAT2)") (class "Default")
      (node (ref "R1") (pin "2") (pinfunction "2_2") (pintype "passive"))
      (node (ref "U$1") (pin "1") (pinfunction "DAT2_1") (pintype "bidirectional"))
    )
    (net (code "70") (name "Net-(U1-BOOT)") (class "Default")
      (node (ref "C4") (pin "2") (pinfunction "2_2") (pintype "passive"))
      (node (ref "U1") (pin "1") (pinfunction "BOOT_1") (pintype "input"))
    )
    (net (code "71") (name "Net-(U1-COMP)") (class "Default")
      (node (ref "C2") (pin "1") (pinfunction "1_1") (pintype "passive"))
      (node (ref "C3") (pin "1") (pinfunction "1_1") (pintype "passive"))
      (node (ref "U1") (pin "6") (pinfunction "COMP_6") (pintype "output"))
    )
    (net (code "72") (name "Net-(U1-EN)") (class "Default")
      (node (ref "R19") (pin "2") (pinfunction "2_2") (pintype "passive"))
      (node (ref "R21") (pin "2") (pinfunction "2_2") (pintype "passive"))
      (node (ref "U1") (pin "3") (pinfunction "EN_3") (pintype "input"))
    )
    (net (code "73") (name "Net-(U1-SS)") (class "Default")
      (node (ref "C1") (pin "1") (pinfunction "1_1") (pintype "passive"))
      (node (ref "U1") (pin "4") (pinfunction "SS_4") (pintype "input"))
    )
    (net (code "74") (name "Net-(U1-VIN)") (class "Default")
      (node (ref "C15") (pin "1") (pinfunction "1_1") (pintype "passive"))
      (node (ref "C16") (pin "1") (pinfunction "1_1") (pintype "passive"))
      (node (ref "D10") (pin "C") (pinfunction "C_C") (pintype "passive"))
      (node (ref "R19") (pin "1") (pinfunction "1_1") (pintype "passive"))
      (node (ref "U1") (pin "2") (pinfunction "VIN_2") (pintype "input"))
    )
    (net (code "75") (name "PH") (class "Default")
      (node (ref "C4") (pin "1") (pinfunction "1_1") (pintype "passive"))
      (node (ref "D9") (pin "C") (pinfunction "C_C") (pintype "passive"))
      (node (ref "L2") (pin "1") (pinfunction "1_1") (pintype "passive"))
      (node (ref "U1") (pin "8") (pinfunction "PH_8") (pintype "input"))
    )
    (net (code "76") (name "RXD0") (class "Default")
      (node (ref "J6") (pin "1") (pinfunction "1_1") (pintype "passive"))
      (node (ref "JP4") (pin "1") (pinfunction "1_1") (pintype "passive"))
      (node (ref "U5") (pin "40") (pinfunction "RXD0_40") (pintype "bidirectional"))
    )
    (net (code "77") (name "SD") (class "Default")
      (node (ref "R1") (pin "1") (pinfunction "1_1") (pintype "passive"))
      (node (ref "R16") (pin "1") (pinfunction "1_1") (pintype "passive"))
      (node (ref "R17") (pin "1") (pinfunction "1_1") (pintype "passive"))
      (node (ref "R18") (pin "1") (pinfunction "1_1") (pintype "passive"))
      (node (ref "R2") (pin "1") (pinfunction "1_1") (pintype "passive"))
      (node (ref "R20") (pin "1") (pinfunction "1_1") (pintype "passive"))
      (node (ref "R6") (pin "1") (pinfunction "1_1") (pintype "passive"))
      (node (ref "S4") (pin "2") (pinfunction "2_2") (pintype "passive"))
      (node (ref "U$1") (pin "4") (pinfunction "VDD_4") (pintype "bidirectional"))
    )
    (net (code "78") (name "TXD0") (class "Default")
      (node (ref "J6") (pin "2") (pinfunction "2_2") (pintype "passive"))
      (node (ref "JP4") (pin "2") (pinfunction "2_2") (pintype "passive"))
      (node (ref "U5") (pin "39") (pinfunction "TXD0_39") (pintype "bidirectional"))
    )
    (net (code "79") (name "VB1") (class "Default")
      (node (ref "C51") (pin "1") (pinfunction "1_1") (pintype "passive"))
      (node (ref "D7") (pin "C") (pinfunction "C_C") (pintype "passive"))
      (node (ref "U7") (pin "20") (pinfunction "VB1_20") (pintype "power_in"))
    )
    (net (code "80") (name "VB2") (class "Default")
      (node (ref "C52") (pin "1") (pinfunction "1_1") (pintype "passive"))
      (node (ref "D8") (pin "C") (pinfunction "C_C") (pintype "passive"))
      (node (ref "U7") (pin "17") (pinfunction "VB2_17") (pintype "power_in"))
    )
    (net (code "81") (name "VB3") (class "Default")
      (node (ref "C53") (pin "1") (pinfunction "1_1") (pintype "passive"))
      (node (ref "D11") (pin "C") (pinfunction "C_C") (pintype "passive"))
      (node (ref "U7") (pin "14") (pinfunction "VB3_14") (pintype "power_in"))
    )
    (net (code "82") (name "VBUS") (class "Default")
      (node (ref "D3") (pin "A") (pinfunction "A_A") (pintype "passive"))
      (node (ref "J2") (pin "A4_B9") (pinfunction "VBUS_A4_B9") (pintype "power_in"))
      (node (ref "J2") (pin "B4_A9") (pinfunction "VBUS_B4_A9") (pintype "power_in"))
      (node (ref "R27") (pin "1") (pinfunction "1_1") (pintype "passive"))
    )
    (net (code "83") (name "VCC") (class "Default")
      (node (ref "C11") (pin "2") (pinfunction "2_2") (pintype "passive"))
      (node (ref "C12") (pin "2") (pinfunction "2_2") (pintype "passive"))
      (node (ref "C13") (pin "2") (pinfunction "2_2") (pintype "passive"))
      (node (ref "C14") (pin "2") (pinfunction "2_2") (pintype "passive"))
      (node (ref "C27") (pin "2") (pinfunction "2_2") (pintype "passive"))
      (node (ref "C28") (pin "2") (pinfunction "2_2") (pintype "passive"))
      (node (ref "C29") (pin "2") (pinfunction "2_2") (pintype "passive"))
      (node (ref "C30") (pin "2") (pinfunction "2_2") (pintype "passive"))
      (node (ref "C31") (pin "1") (pinfunction "1_1") (pintype "passive"))
      (node (ref "C32") (pin "1") (pinfunction "1_1") (pintype "passive"))
      (node (ref "C33") (pin "1") (pinfunction "1_1") (pintype "passive"))
      (node (ref "C34") (pin "1") (pinfunction "1_1") (pintype "passive"))
      (node (ref "C35") (pin "1") (pinfunction "1_1") (pintype "passive"))
      (node (ref "C36") (pin "1") (pinfunction "1_1") (pintype "passive"))
      (node (ref "C38") (pin "1") (pinfunction "1_1") (pintype "passive"))
      (node (ref "C39") (pin "1") (pinfunction "1_1") (pintype "passive"))
      (node (ref "C40") (pin "1") (pinfunction "1_1") (pintype "passive"))
      (node (ref "C41") (pin "1") (pinfunction "1_1") (pintype "passive"))
      (node (ref "C42") (pin "1") (pinfunction "1_1") (pintype "passive"))
      (node (ref "C43") (pin "1") (pinfunction "1_1") (pintype "passive"))
      (node (ref "C44") (pin "1") (pinfunction "1_1") (pintype "passive"))
      (node (ref "C45") (pin "1") (pinfunction "1_1") (pintype "passive"))
      (node (ref "C46") (pin "1") (pinfunction "1_1") (pintype "passive"))
      (node (ref "C50") (pin "2") (pinfunction "2_2") (pintype "passive"))
      (node (ref "C55") (pin "1") (pinfunction "1_1") (pintype "passive"))
      (node (ref "C7") (pin "2") (pinfunction "2_2") (pintype "passive"))
      (node (ref "C8") (pin "2") (pinfunction "2_2") (pintype "passive"))
      (node (ref "D10") (pin "A") (pinfunction "A_A") (pintype "passive"))
      (node (ref "D11") (pin "A") (pinfunction "A_A") (pintype "passive"))
      (node (ref "D7") (pin "A") (pinfunction "A_A") (pintype "passive"))
      (node (ref "D8") (pin "A") (pinfunction "A_A") (pintype "passive"))
      (node (ref "J1") (pin "1") (pinfunction "1_1") (pintype "passive"))
      (node (ref "J6") (pin "12") (pinfunction "12_12") (pintype "passive"))
      (node (ref "JP3") (pin "1") (pinfunction "1_1") (pintype "passive"))
      (node (ref "JP3") (pin "2") (pinfunction "2_2") (pintype "passive"))
      (node (ref "JP3") (pin "3") (pinfunction "3_3") (pintype "passive"))
      (node (ref "Q16") (pin "2") (pinfunction "D1_1_2") (pintype "bidirectional"))
      (node (ref "Q16") (pin "3") (pinfunction "D1_2_3") (pintype "bidirectional"))
      (node (ref "Q16") (pin "4") (pinfunction "D1_3_4") (pintype "bidirectional"))
      (node (ref "Q16") (pin "9") (pinfunction "D1_4_9") (pintype "bidirectional"))
      (node (ref "Q17") (pin "2") (pinfunction "D1_1_2") (pintype "bidirectional"))
      (node (ref "Q17") (pin "3") (pinfunction "D1_2_3") (pintype "bidirectional"))
      (node (ref "Q17") (pin "4") (pinfunction "D1_3_4") (pintype "bidirectional"))
      (node (ref "Q17") (pin "9") (pinfunction "D1_4_9") (pintype "bidirectional"))
      (node (ref "Q4") (pin "2") (pinfunction "D1_1_2") (pintype "bidirectional"))
      (node (ref "Q4") (pin "3") (pinfunction "D1_2_3") (pintype "bidirectional"))
      (node (ref "Q4") (pin "4") (pinfunction "D1_3_4") (pintype "bidirectional"))
      (node (ref "Q4") (pin "9") (pinfunction "D1_4_9") (pintype "bidirectional"))
      (node (ref "R23") (pin "1") (pinfunction "1_1") (pintype "passive"))
      (node (ref "U7") (pin "4") (pinfunction "VCC_4") (pintype "power_in"))
      (node (ref "VCC") (pin "1") (pinfunction "P_1") (pintype "passive"))
    )
    (net (code "84") (name "VS1") (class "Default")
      (node (ref "A") (pin "1") (pinfunction "P_1") (pintype "passive"))
      (node (ref "C51") (pin "2") (pinfunction "2_2") (pintype "passive"))
      (node (ref "Q4") (pin "10") (pinfunction "S1/D2_10") (pintype "bidirectional"))
      (node (ref "U7") (pin "18") (pinfunction "VS1_18") (pintype "power_in"))
    )
    (net (code "85") (name "VS2") (class "Default")
      (node (ref "C22") (pin "2") (pinfunction "2_2") (pintype "passive"))
      (node (ref "C23") (pin "2") (pinfunction "2_2") (pintype "passive"))
      (node (ref "C52") (pin "2") (pinfunction "2_2") (pintype "passive"))
      (node (ref "Q16") (pin "10") (pinfunction "S1/D2_10") (pintype "bidirectional"))
      (node (ref "U7") (pin "15") (pinfunction "VS2_15") (pintype "power_in"))
    )
    (net (code "86") (name "VS3") (class "Default")
      (node (ref "C") (pin "1") (pinfunction "P_1") (pintype "passive"))
      (node (ref "C53") (pin "2") (pinfunction "2_2") (pintype "passive"))
      (node (ref "Q17") (pin "10") (pinfunction "S1/D2_10") (pintype "bidirectional"))
      (node (ref "U7") (pin "12") (pinfunction "VS3_12") (pintype "power_in"))
    )
    (net (code "87") (name "VSENSE") (class "Default")
      (node (ref "R24B") (pin "1") (pinfunction "1_1") (pintype "passive"))
      (node (ref "R25") (pin "2") (pinfunction "2_2") (pintype "passive"))
      (node (ref "U1") (pin "5") (pinfunction "VSENSE_5") (pintype "input"))
    )
    (net (code "88") (name "unconnected-(J2-SBU1-PadA8)") (class "Default")
      (node (ref "J2") (pin "A8") (pinfunction "SBU1_A8") (pintype "bidirectional"))
    )
    (net (code "89") (name "unconnected-(J2-SBU2-PadB8)") (class "Default")
      (node (ref "J2") (pin "B8") (pinfunction "SBU2_B8") (pintype "bidirectional"))
    )
    (net (code "90") (name "unconnected-(S3-Pad3)") (class "Default")
      (node (ref "S3") (pin "3") (pinfunction "3_3") (pintype "passive"))
    )
    (net (code "91") (name "unconnected-(S4-Pad3)") (class "Default")
      (node (ref "S4") (pin "3") (pinfunction "3_3") (pintype "passive"))
    )
    (net (code "92") (name "unconnected-(U$1-PadCD)") (class "Default")
      (node (ref "U$1") (pin "CD") (pinfunction "CD_CD") (pintype "bidirectional"))
    )
    (net (code "93") (name "unconnected-(U3-2A-Pad3)") (class "Default")
      (node (ref "U3") (pin "3") (pinfunction "2A_3") (pintype "input"))
    )
    (net (code "94") (name "unconnected-(U3-2Y-Pad4)") (class "Default")
      (node (ref "U3") (pin "4") (pinfunction "2Y_4") (pintype "output"))
    )
  )
)
